# right.net
KiCad netlist of a schematic drawn in EAGLE
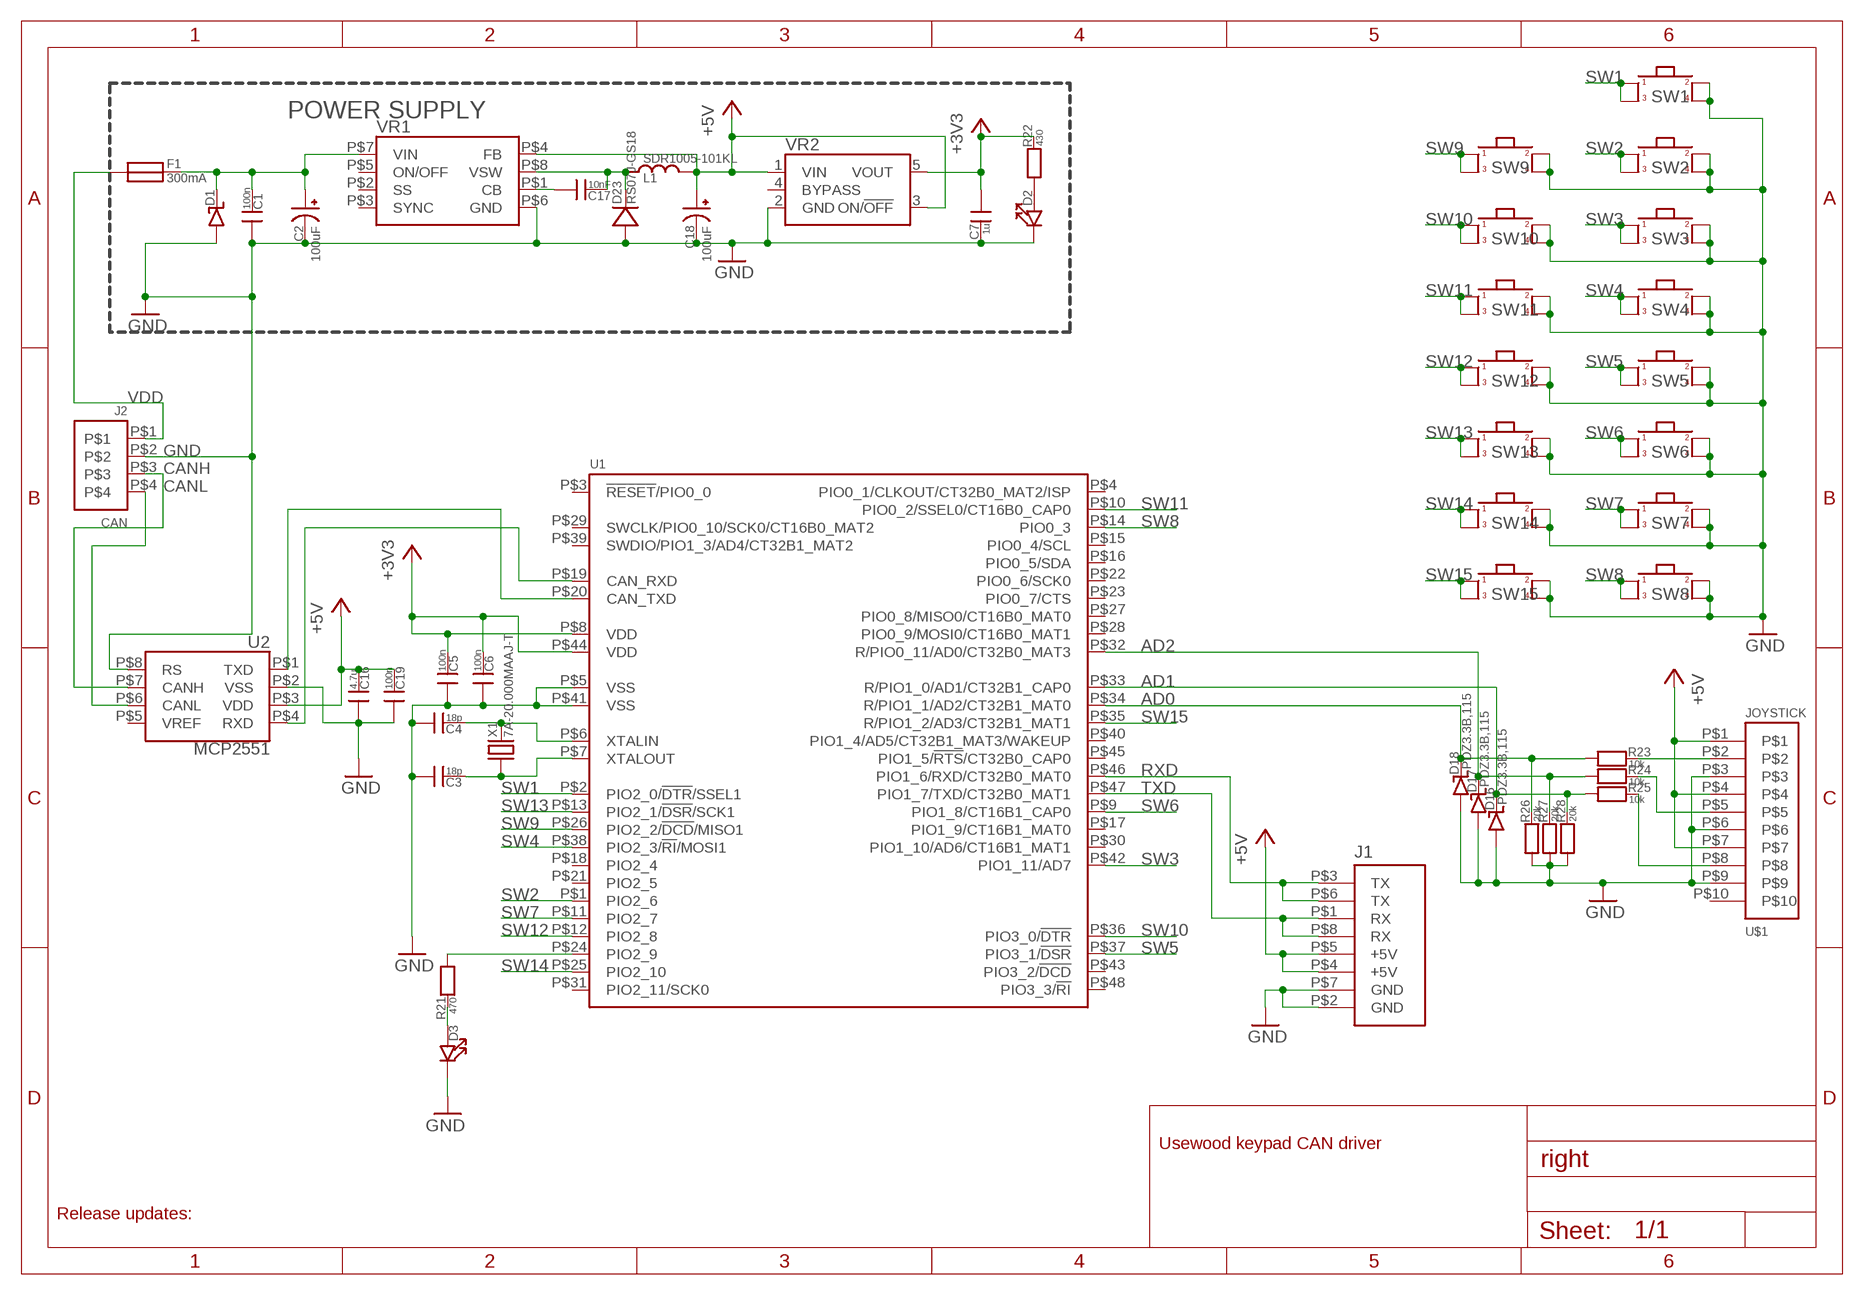
[diagram p0: schematic, sheet 1]

(export (version "E")
  (design (tool "Eeschema 10.0.6"))
  (components
    (comp (ref "C1")
      (value "100n")
      (footprint "eagle-import:0603_SILKSCREEN")
      (libsource (lib "eagle-import") (part "CAP_0603"))
    )
    (comp (ref "C2")
      (value "100uF")
      (footprint "eagle-import:CAP_POL_SMD_10X10X10MM")
      (libsource (lib "eagle-import") (part "CAP_POLSMD_10X10X10MM"))
    )
    (comp (ref "C3")
      (value "18p")
      (footprint "eagle-import:0603_SILKSCREEN")
      (libsource (lib "eagle-import") (part "CAP_0603"))
    )
    (comp (ref "C4")
      (value "18p")
      (footprint "eagle-import:0603_SILKSCREEN")
      (libsource (lib "eagle-import") (part "CAP_0603"))
    )
    (comp (ref "C5")
      (value "100n")
      (footprint "eagle-import:0603_SILKSCREEN")
      (libsource (lib "eagle-import") (part "CAP_0603"))
    )
    (comp (ref "C6")
      (value "100n")
      (footprint "eagle-import:0603_SILKSCREEN")
      (libsource (lib "eagle-import") (part "CAP_0603"))
    )
    (comp (ref "C7")
      (value "1u")
      (footprint "eagle-import:0603_SILKSCREEN")
      (libsource (lib "eagle-import") (part "CAP_0603"))
    )
    (comp (ref "C16")
      (value "4.7u")
      (footprint "eagle-import:0603_SILKSCREEN")
      (libsource (lib "eagle-import") (part "CAP_0603"))
    )
    (comp (ref "C17")
      (value "10nF")
      (footprint "eagle-import:0603_SILKSCREEN")
      (libsource (lib "eagle-import") (part "CAP_0603"))
    )
    (comp (ref "C18")
      (value "100uF")
      (footprint "eagle-import:CAP_POL_SMD_10X10X10MM")
      (libsource (lib "eagle-import") (part "CAP_POLSMD_10X10X10MM"))
    )
    (comp (ref "C19")
      (value "100n")
      (footprint "eagle-import:0603_SILKSCREEN")
      (libsource (lib "eagle-import") (part "CAP_0603"))
    )
    (comp (ref "D1")
      (value "DIODE_TVS_SMBJ33A-TRDO-214AA")
      (footprint "eagle-import:DO-214AA")
      (libsource (lib "eagle-import") (part "DIODE_TVS_SMBJ33A-TRDO-214AA"))
    )
    (comp (ref "D2")
      (value "LED_0603")
      (footprint "eagle-import:0603_SILKSCREEN")
      (libsource (lib "eagle-import") (part "LED_0603"))
    )
    (comp (ref "D3")
      (value "LED_0603")
      (footprint "eagle-import:0603_SILKSCREEN")
      (libsource (lib "eagle-import") (part "LED_0603"))
    )
    (comp (ref "D16")
      (value "PDZ3.3B,115")
      (footprint "eagle-import:SOD123")
      (libsource (lib "eagle-import") (part "DIODE_ZENERSDO123"))
    )
    (comp (ref "D17")
      (value "PDZ3.3B,115")
      (footprint "eagle-import:SOD123")
      (libsource (lib "eagle-import") (part "DIODE_ZENERSDO123"))
    )
    (comp (ref "D18")
      (value "PDZ3.3B,115")
      (footprint "eagle-import:SOD123")
      (libsource (lib "eagle-import") (part "DIODE_ZENERSDO123"))
    )
    (comp (ref "D23")
      (value "RS07J-GS18")
      (footprint "eagle-import:DO219AB")
      (libsource (lib "eagle-import") (part "DIODEDO219AB"))
    )
    (comp (ref "F1")
      (value "300mA")
      (footprint "eagle-import:FUSE_100MA")
      (libsource (lib "eagle-import") (part "FUSE_MC36204_100MA"))
    )
    (comp (ref "J1")
      (value "HEADER_USART_2_SMD")
      (footprint "eagle-import:HEADER_4_2_SMD")
      (libsource (lib "eagle-import") (part "HEADER_USART_2_SMD"))
    )
    (comp (ref "J2")
      (value "CAN")
      (footprint "eagle-import:MOLEX_MICRO_FIT_4WAY_SMD")
      (libsource (lib "eagle-import") (part "MOLEX_MICRO-FIT_4WAY_SMD"))
    )
    (comp (ref "L1")
      (value "SDR1005-101KL")
      (footprint "eagle-import:INDUCTOR_BOURNS_10X13X5MM")
      (libsource (lib "eagle-import") (part "INDUCTORBOURNS_10X13X5MM"))
    )
    (comp (ref "R21")
      (value "470")
      (footprint "eagle-import:0603_SILKSCREEN")
      (libsource (lib "eagle-import") (part "RES_0603"))
    )
    (comp (ref "R22")
      (value "430")
      (footprint "eagle-import:0603_SILKSCREEN")
      (libsource (lib "eagle-import") (part "RES_0603"))
    )
    (comp (ref "R23")
      (value "10k")
      (footprint "eagle-import:0603_SILKSCREEN")
      (libsource (lib "eagle-import") (part "RES_0603"))
    )
    (comp (ref "R24")
      (value "10k")
      (footprint "eagle-import:0603_SILKSCREEN")
      (libsource (lib "eagle-import") (part "RES_0603"))
    )
    (comp (ref "R25")
      (value "10k")
      (footprint "eagle-import:0603_SILKSCREEN")
      (libsource (lib "eagle-import") (part "RES_0603"))
    )
    (comp (ref "R26")
      (value "20k")
      (footprint "eagle-import:0603_SILKSCREEN")
      (libsource (lib "eagle-import") (part "RES_0603"))
    )
    (comp (ref "R27")
      (value "20k")
      (footprint "eagle-import:0603_SILKSCREEN")
      (libsource (lib "eagle-import") (part "RES_0603"))
    )
    (comp (ref "R28")
      (value "20k")
      (footprint "eagle-import:0603_SILKSCREEN")
      (libsource (lib "eagle-import") (part "RES_0603"))
    )
    (comp (ref "SW1")
      (value "SWITCH_KMR231G")
      (footprint "eagle-import:SWITCH_KMR231")
      (libsource (lib "eagle-import") (part "SWITCH_KMR231G"))
    )
    (comp (ref "SW2")
      (value "SWITCH_KMR231G")
      (footprint "eagle-import:SWITCH_KMR231")
      (libsource (lib "eagle-import") (part "SWITCH_KMR231G"))
    )
    (comp (ref "SW3")
      (value "SWITCH_KMR231G")
      (footprint "eagle-import:SWITCH_KMR231")
      (libsource (lib "eagle-import") (part "SWITCH_KMR231G"))
    )
    (comp (ref "SW4")
      (value "SWITCH_KMR231G")
      (footprint "eagle-import:SWITCH_KMR231")
      (libsource (lib "eagle-import") (part "SWITCH_KMR231G"))
    )
    (comp (ref "SW5")
      (value "SWITCH_KMR231G")
      (footprint "eagle-import:SWITCH_KMR231")
      (libsource (lib "eagle-import") (part "SWITCH_KMR231G"))
    )
    (comp (ref "SW6")
      (value "SWITCH_KMR231G")
      (footprint "eagle-import:SWITCH_KMR231")
      (libsource (lib "eagle-import") (part "SWITCH_KMR231G"))
    )
    (comp (ref "SW7")
      (value "SWITCH_KMR231G")
      (footprint "eagle-import:SWITCH_KMR231")
      (libsource (lib "eagle-import") (part "SWITCH_KMR231G"))
    )
    (comp (ref "SW8")
      (value "SWITCH_KMR231G")
      (footprint "eagle-import:SWITCH_KMR231")
      (libsource (lib "eagle-import") (part "SWITCH_KMR231G"))
    )
    (comp (ref "SW9")
      (value "SWITCH_KMR231G")
      (footprint "eagle-import:SWITCH_KMR231")
      (libsource (lib "eagle-import") (part "SWITCH_KMR231G"))
    )
    (comp (ref "SW10")
      (value "SWITCH_KMR231G")
      (footprint "eagle-import:SWITCH_KMR231")
      (libsource (lib "eagle-import") (part "SWITCH_KMR231G"))
    )
    (comp (ref "SW11")
      (value "SWITCH_KMR231G")
      (footprint "eagle-import:SWITCH_KMR231")
      (libsource (lib "eagle-import") (part "SWITCH_KMR231G"))
    )
    (comp (ref "SW12")
      (value "SWITCH_KMR231G")
      (footprint "eagle-import:SWITCH_KMR231")
      (libsource (lib "eagle-import") (part "SWITCH_KMR231G"))
    )
    (comp (ref "SW13")
      (value "SWITCH_KMR231G")
      (footprint "eagle-import:SWITCH_KMR231")
      (libsource (lib "eagle-import") (part "SWITCH_KMR231G"))
    )
    (comp (ref "SW14")
      (value "SWITCH_KMR231G")
      (footprint "eagle-import:SWITCH_KMR231")
      (libsource (lib "eagle-import") (part "SWITCH_KMR231G"))
    )
    (comp (ref "SW15")
      (value "SWITCH_KMR231G")
      (footprint "eagle-import:SWITCH_KMR231")
      (libsource (lib "eagle-import") (part "SWITCH_KMR231G"))
    )
    (comp (ref "U$1")
      (value "JOYSTICK")
      (footprint "eagle-import:MOLEX-MICRO-FIT_10WAY")
      (libsource (lib "eagle-import") (part "MOLEX_MICRO-FIT_10WAY_TH"))
    )
    (comp (ref "U1")
      (value "LPC11C14_QFP48")
      (footprint "eagle-import:QFP48")
      (libsource (lib "eagle-import") (part "LPC11C14_QFP48"))
    )
    (comp (ref "U2")
      (value "MCP2551")
      (footprint "eagle-import:SOIC8")
      (libsource (lib "eagle-import") (part "MCP2551_SOIC8"))
    )
    (comp (ref "VR1")
      (value "LM2671SOIC8")
      (footprint "eagle-import:SOIC8")
      (libsource (lib "eagle-import") (part "LM2671SOIC8"))
    )
    (comp (ref "VR2")
      (value "REG_LP2985_SOP5")
      (footprint "eagle-import:SOP5")
      (libsource (lib "eagle-import") (part "REG_LP2985_SOP5"))
    )
    (comp (ref "X1")
      (value "7A-20.000MAAJ-T")
      (footprint "eagle-import:XTAL_SMD_5X3.2")
      (libsource (lib "eagle-import") (part "XTAL_7A-12.000MAAJ-T"))
    )
  )
  (nets
    (net (code "1") (name "+3V3") (class "Default")
      (node (ref "C5") (pin "1") (pinfunction "P$2_1") (pintype "bidirectional"))
      (node (ref "C6") (pin "1") (pinfunction "P$2_1") (pintype "bidirectional"))
      (node (ref "C7") (pin "0") (pinfunction "P$1_0") (pintype "bidirectional"))
      (node (ref "R22") (pin "1") (pinfunction "P$2_1") (pintype "bidirectional"))
      (node (ref "U1") (pin "P$44") (pinfunction "VDD_P$44") (pintype "bidirectional"))
      (node (ref "U1") (pin "P$8") (pinfunction "VDD_P$8") (pintype "bidirectional"))
      (node (ref "VR2") (pin "5") (pinfunction "VOUT_5") (pintype "bidirectional"))
    )
    (net (code "2") (name "+5V") (class "Default")
      (node (ref "C16") (pin "1") (pinfunction "P$2_1") (pintype "bidirectional"))
      (node (ref "C18") (pin "+") (pinfunction "+_+") (pintype "bidirectional"))
      (node (ref "C19") (pin "1") (pinfunction "P$2_1") (pintype "bidirectional"))
      (node (ref "J1") (pin "P$4") (pinfunction "+5V_P$4") (pintype "bidirectional"))
      (node (ref "J1") (pin "P$5") (pinfunction "+5V_P$5") (pintype "bidirectional"))
      (node (ref "L1") (pin "P$2") (pinfunction "P$2_P$2") (pintype "bidirectional"))
      (node (ref "U$1") (pin "P$1") (pinfunction "P$1_P$1") (pintype "bidirectional"))
      (node (ref "U$1") (pin "P$4") (pinfunction "P$4_P$4") (pintype "bidirectional"))
      (node (ref "U$1") (pin "P$7") (pinfunction "P$7_P$7") (pintype "bidirectional"))
      (node (ref "U2") (pin "P$3") (pinfunction "VDD_P$3") (pintype "bidirectional"))
      (node (ref "VR1") (pin "P$4") (pinfunction "FB_P$4") (pintype "bidirectional"))
      (node (ref "VR2") (pin "1") (pinfunction "VIN_1") (pintype "bidirectional"))
      (node (ref "VR2") (pin "3") (pinfunction "ON/~{OFF}_3") (pintype "bidirectional"))
    )
    (net (code "3") (name "/AD0") (class "Default")
      (node (ref "D18") (pin "P$2") (pinfunction "N_P$2") (pintype "bidirectional"))
      (node (ref "R23") (pin "0") (pinfunction "P$1_0") (pintype "bidirectional"))
      (node (ref "R26") (pin "1") (pinfunction "P$2_1") (pintype "bidirectional"))
      (node (ref "U1") (pin "P$34") (pinfunction "R/PIO1_1/AD2/CT32B1_MAT0_P$34") (pintype "bidirectional"))
    )
    (net (code "4") (name "/AD1") (class "Default")
      (node (ref "D16") (pin "P$2") (pinfunction "N_P$2") (pintype "bidirectional"))
      (node (ref "R25") (pin "0") (pinfunction "P$1_0") (pintype "bidirectional"))
      (node (ref "R28") (pin "1") (pinfunction "P$2_1") (pintype "bidirectional"))
      (node (ref "U1") (pin "P$33") (pinfunction "R/PIO1_0/AD1/CT32B1_CAP0_P$33") (pintype "bidirectional"))
    )
    (net (code "5") (name "/AD2") (class "Default")
      (node (ref "D17") (pin "P$2") (pinfunction "N_P$2") (pintype "bidirectional"))
      (node (ref "R24") (pin "0") (pinfunction "P$1_0") (pintype "bidirectional"))
      (node (ref "R27") (pin "1") (pinfunction "P$2_1") (pintype "bidirectional"))
      (node (ref "U1") (pin "P$32") (pinfunction "R/PIO0_11/AD0/CT32B0_MAT3_P$32") (pintype "bidirectional"))
    )
    (net (code "6") (name "/CANH") (class "Default")
      (node (ref "J2") (pin "P$3") (pinfunction "P$3_P$3") (pintype "bidirectional"))
      (node (ref "U2") (pin "P$7") (pinfunction "CANH_P$7") (pintype "bidirectional"))
    )
    (net (code "7") (name "/CANL") (class "Default")
      (node (ref "J2") (pin "P$4") (pinfunction "P$4_P$4") (pintype "bidirectional"))
      (node (ref "U2") (pin "P$6") (pinfunction "CANL_P$6") (pintype "bidirectional"))
    )
    (net (code "8") (name "/RXD") (class "Default")
      (node (ref "J1") (pin "P$3") (pinfunction "TX_P$3") (pintype "bidirectional"))
      (node (ref "J1") (pin "P$6") (pinfunction "TX_P$6") (pintype "bidirectional"))
      (node (ref "U1") (pin "P$46") (pinfunction "PIO1_6/RXD/CT32B0_MAT0_P$46") (pintype "bidirectional"))
    )
    (net (code "9") (name "/SW1") (class "Default")
      (node (ref "SW1") (pin "P$1") (pinfunction "P$1_P$1") (pintype "bidirectional"))
      (node (ref "SW1") (pin "P$3") (pinfunction "P$3_P$3") (pintype "bidirectional"))
      (node (ref "U1") (pin "P$2") (pinfunction "PIO2_0/~{DTR}/SSEL1_P$2") (pintype "bidirectional"))
    )
    (net (code "10") (name "/SW2") (class "Default")
      (node (ref "SW2") (pin "P$1") (pinfunction "P$1_P$1") (pintype "bidirectional"))
      (node (ref "SW2") (pin "P$3") (pinfunction "P$3_P$3") (pintype "bidirectional"))
      (node (ref "U1") (pin "P$1") (pinfunction "PIO2_6_P$1") (pintype "bidirectional"))
    )
    (net (code "11") (name "/SW3") (class "Default")
      (node (ref "SW3") (pin "P$1") (pinfunction "P$1_P$1") (pintype "bidirectional"))
      (node (ref "SW3") (pin "P$3") (pinfunction "P$3_P$3") (pintype "bidirectional"))
      (node (ref "U1") (pin "P$42") (pinfunction "PIO1_11/AD7_P$42") (pintype "bidirectional"))
    )
    (net (code "12") (name "/SW4") (class "Default")
      (node (ref "SW4") (pin "P$1") (pinfunction "P$1_P$1") (pintype "bidirectional"))
      (node (ref "SW4") (pin "P$3") (pinfunction "P$3_P$3") (pintype "bidirectional"))
      (node (ref "U1") (pin "P$38") (pinfunction "PIO2_3/~{RI}/MOSI1_P$38") (pintype "bidirectional"))
    )
    (net (code "13") (name "/SW5") (class "Default")
      (node (ref "SW5") (pin "P$1") (pinfunction "P$1_P$1") (pintype "bidirectional"))
      (node (ref "SW5") (pin "P$3") (pinfunction "P$3_P$3") (pintype "bidirectional"))
      (node (ref "U1") (pin "P$37") (pinfunction "PIO3_1/~{DSR}_P$37") (pintype "bidirectional"))
    )
    (net (code "14") (name "/SW6") (class "Default")
      (node (ref "SW6") (pin "P$1") (pinfunction "P$1_P$1") (pintype "bidirectional"))
      (node (ref "SW6") (pin "P$3") (pinfunction "P$3_P$3") (pintype "bidirectional"))
      (node (ref "U1") (pin "P$9") (pinfunction "PIO1_8/CT16B1_CAP0_P$9") (pintype "bidirectional"))
    )
    (net (code "15") (name "/SW7") (class "Default")
      (node (ref "SW7") (pin "P$1") (pinfunction "P$1_P$1") (pintype "bidirectional"))
      (node (ref "SW7") (pin "P$3") (pinfunction "P$3_P$3") (pintype "bidirectional"))
      (node (ref "U1") (pin "P$11") (pinfunction "PIO2_7_P$11") (pintype "bidirectional"))
    )
    (net (code "16") (name "/SW8") (class "Default")
      (node (ref "SW8") (pin "P$1") (pinfunction "P$1_P$1") (pintype "bidirectional"))
      (node (ref "SW8") (pin "P$3") (pinfunction "P$3_P$3") (pintype "bidirectional"))
      (node (ref "U1") (pin "P$14") (pinfunction "PIO0_3_P$14") (pintype "bidirectional"))
    )
    (net (code "17") (name "/SW9") (class "Default")
      (node (ref "SW9") (pin "P$1") (pinfunction "P$1_P$1") (pintype "bidirectional"))
      (node (ref "SW9") (pin "P$3") (pinfunction "P$3_P$3") (pintype "bidirectional"))
      (node (ref "U1") (pin "P$26") (pinfunction "PIO2_2/~{DCD}/MISO1_P$26") (pintype "bidirectional"))
    )
    (net (code "18") (name "/SW10") (class "Default")
      (node (ref "SW10") (pin "P$1") (pinfunction "P$1_P$1") (pintype "bidirectional"))
      (node (ref "SW10") (pin "P$3") (pinfunction "P$3_P$3") (pintype "bidirectional"))
      (node (ref "U1") (pin "P$36") (pinfunction "PIO3_0/~{DTR}_P$36") (pintype "bidirectional"))
    )
    (net (code "19") (name "/SW11") (class "Default")
      (node (ref "SW11") (pin "P$1") (pinfunction "P$1_P$1") (pintype "bidirectional"))
      (node (ref "SW11") (pin "P$3") (pinfunction "P$3_P$3") (pintype "bidirectional"))
      (node (ref "U1") (pin "P$10") (pinfunction "PIO0_2/SSEL0/CT16B0_CAP0_P$10") (pintype "bidirectional"))
    )
    (net (code "20") (name "/SW12") (class "Default")
      (node (ref "SW12") (pin "P$1") (pinfunction "P$1_P$1") (pintype "bidirectional"))
      (node (ref "SW12") (pin "P$3") (pinfunction "P$3_P$3") (pintype "bidirectional"))
      (node (ref "U1") (pin "P$12") (pinfunction "PIO2_8_P$12") (pintype "bidirectional"))
    )
    (net (code "21") (name "/SW13") (class "Default")
      (node (ref "SW13") (pin "P$1") (pinfunction "P$1_P$1") (pintype "bidirectional"))
      (node (ref "SW13") (pin "P$3") (pinfunction "P$3_P$3") (pintype "bidirectional"))
      (node (ref "U1") (pin "P$13") (pinfunction "PIO2_1/~{DSR}/SCK1_P$13") (pintype "bidirectional"))
    )
    (net (code "22") (name "/SW14") (class "Default")
      (node (ref "SW14") (pin "P$1") (pinfunction "P$1_P$1") (pintype "bidirectional"))
      (node (ref "SW14") (pin "P$3") (pinfunction "P$3_P$3") (pintype "bidirectional"))
      (node (ref "U1") (pin "P$25") (pinfunction "PIO2_10_P$25") (pintype "bidirectional"))
    )
    (net (code "23") (name "/SW15") (class "Default")
      (node (ref "SW15") (pin "P$1") (pinfunction "P$1_P$1") (pintype "bidirectional"))
      (node (ref "SW15") (pin "P$3") (pinfunction "P$3_P$3") (pintype "bidirectional"))
      (node (ref "U1") (pin "P$35") (pinfunction "R/PIO1_2/AD3/CT32B1_MAT1_P$35") (pintype "bidirectional"))
    )
    (net (code "24") (name "/TXD") (class "Default")
      (node (ref "J1") (pin "P$1") (pinfunction "RX_P$1") (pintype "bidirectional"))
      (node (ref "J1") (pin "P$8") (pinfunction "RX_P$8") (pintype "bidirectional"))
      (node (ref "U1") (pin "P$47") (pinfunction "PIO1_7/TXD/CT32B0_MAT1_P$47") (pintype "bidirectional"))
    )
    (net (code "25") (name "/VDD") (class "Default")
      (node (ref "F1") (pin "P$1") (pinfunction "P$1_P$1") (pintype "bidirectional"))
      (node (ref "J2") (pin "P$1") (pinfunction "P$1_P$1") (pintype "bidirectional"))
    )
    (net (code "26") (name "GND") (class "Default")
      (node (ref "C1") (pin "0") (pinfunction "P$1_0") (pintype "bidirectional"))
      (node (ref "C16") (pin "0") (pinfunction "P$1_0") (pintype "bidirectional"))
      (node (ref "C18") (pin "-") (pinfunction "-_-") (pintype "bidirectional"))
      (node (ref "C19") (pin "0") (pinfunction "P$1_0") (pintype "bidirectional"))
      (node (ref "C2") (pin "-") (pinfunction "-_-") (pintype "bidirectional"))
      (node (ref "C3") (pin "0") (pinfunction "P$1_0") (pintype "bidirectional"))
      (node (ref "C4") (pin "0") (pinfunction "P$1_0") (pintype "bidirectional"))
      (node (ref "C5") (pin "0") (pinfunction "P$1_0") (pintype "bidirectional"))
      (node (ref "C6") (pin "0") (pinfunction "P$1_0") (pintype "bidirectional"))
      (node (ref "C7") (pin "1") (pinfunction "P$2_1") (pintype "bidirectional"))
      (node (ref "D1") (pin "P$1") (pinfunction "P_P$1") (pintype "bidirectional"))
      (node (ref "D16") (pin "P$1") (pinfunction "P_P$1") (pintype "bidirectional"))
      (node (ref "D17") (pin "P$1") (pinfunction "P_P$1") (pintype "bidirectional"))
      (node (ref "D18") (pin "P$1") (pinfunction "P_P$1") (pintype "bidirectional"))
      (node (ref "D2") (pin "1") (pinfunction "1_1") (pintype "bidirectional"))
      (node (ref "D23") (pin "P$1") (pinfunction "P_P$1") (pintype "bidirectional"))
      (node (ref "D3") (pin "1") (pinfunction "1_1") (pintype "bidirectional"))
      (node (ref "J1") (pin "P$2") (pinfunction "GND_P$2") (pintype "bidirectional"))
      (node (ref "J1") (pin "P$7") (pinfunction "GND_P$7") (pintype "bidirectional"))
      (node (ref "J2") (pin "P$2") (pinfunction "P$2_P$2") (pintype "bidirectional"))
      (node (ref "R26") (pin "0") (pinfunction "P$1_0") (pintype "bidirectional"))
      (node (ref "R27") (pin "0") (pinfunction "P$1_0") (pintype "bidirectional"))
      (node (ref "R28") (pin "0") (pinfunction "P$1_0") (pintype "bidirectional"))
      (node (ref "SW1") (pin "P$2") (pinfunction "P$2_P$2") (pintype "bidirectional"))
      (node (ref "SW1") (pin "P$4") (pinfunction "P$4_P$4") (pintype "bidirectional"))
      (node (ref "SW10") (pin "P$2") (pinfunction "P$2_P$2") (pintype "bidirectional"))
      (node (ref "SW10") (pin "P$4") (pinfunction "P$4_P$4") (pintype "bidirectional"))
      (node (ref "SW11") (pin "P$2") (pinfunction "P$2_P$2") (pintype "bidirectional"))
      (node (ref "SW11") (pin "P$4") (pinfunction "P$4_P$4") (pintype "bidirectional"))
      (node (ref "SW12") (pin "P$2") (pinfunction "P$2_P$2") (pintype "bidirectional"))
      (node (ref "SW12") (pin "P$4") (pinfunction "P$4_P$4") (pintype "bidirectional"))
      (node (ref "SW13") (pin "P$2") (pinfunction "P$2_P$2") (pintype "bidirectional"))
      (node (ref "SW13") (pin "P$4") (pinfunction "P$4_P$4") (pintype "bidirectional"))
      (node (ref "SW14") (pin "P$2") (pinfunction "P$2_P$2") (pintype "bidirectional"))
      (node (ref "SW14") (pin "P$4") (pinfunction "P$4_P$4") (pintype "bidirectional"))
      (node (ref "SW15") (pin "P$2") (pinfunction "P$2_P$2") (pintype "bidirectional"))
      (node (ref "SW15") (pin "P$4") (pinfunction "P$4_P$4") (pintype "bidirectional"))
      (node (ref "SW2") (pin "P$2") (pinfunction "P$2_P$2") (pintype "bidirectional"))
      (node (ref "SW2") (pin "P$4") (pinfunction "P$4_P$4") (pintype "bidirectional"))
      (node (ref "SW3") (pin "P$2") (pinfunction "P$2_P$2") (pintype "bidirectional"))
      (node (ref "SW3") (pin "P$4") (pinfunction "P$4_P$4") (pintype "bidirectional"))
      (node (ref "SW4") (pin "P$2") (pinfunction "P$2_P$2") (pintype "bidirectional"))
      (node (ref "SW4") (pin "P$4") (pinfunction "P$4_P$4") (pintype "bidirectional"))
      (node (ref "SW5") (pin "P$2") (pinfunction "P$2_P$2") (pintype "bidirectional"))
      (node (ref "SW5") (pin "P$4") (pinfunction "P$4_P$4") (pintype "bidirectional"))
      (node (ref "SW6") (pin "P$2") (pinfunction "P$2_P$2") (pintype "bidirectional"))
      (node (ref "SW6") (pin "P$4") (pinfunction "P$4_P$4") (pintype "bidirectional"))
      (node (ref "SW7") (pin "P$2") (pinfunction "P$2_P$2") (pintype "bidirectional"))
      (node (ref "SW7") (pin "P$4") (pinfunction "P$4_P$4") (pintype "bidirectional"))
      (node (ref "SW8") (pin "P$2") (pinfunction "P$2_P$2") (pintype "bidirectional"))
      (node (ref "SW8") (pin "P$4") (pinfunction "P$4_P$4") (pintype "bidirectional"))
      (node (ref "SW9") (pin "P$2") (pinfunction "P$2_P$2") (pintype "bidirectional"))
      (node (ref "SW9") (pin "P$4") (pinfunction "P$4_P$4") (pintype "bidirectional"))
      (node (ref "U$1") (pin "P$3") (pinfunction "P$3_P$3") (pintype "bidirectional"))
      (node (ref "U$1") (pin "P$6") (pinfunction "P$6_P$6") (pintype "bidirectional"))
      (node (ref "U$1") (pin "P$9") (pinfunction "P$9_P$9") (pintype "bidirectional"))
      (node (ref "U1") (pin "P$41") (pinfunction "VSS_P$41") (pintype "bidirectional"))
      (node (ref "U1") (pin "P$5") (pinfunction "VSS_P$5") (pintype "bidirectional"))
      (node (ref "U2") (pin "P$2") (pinfunction "VSS_P$2") (pintype "bidirectional"))
      (node (ref "U2") (pin "P$8") (pinfunction "RS_P$8") (pintype "bidirectional"))
      (node (ref "VR1") (pin "P$6") (pinfunction "GND_P$6") (pintype "bidirectional"))
      (node (ref "VR2") (pin "2") (pinfunction "GND_2") (pintype "bidirectional"))
    )
    (net (code "27") (name "Net-(C1-P$2)") (class "Default")
      (node (ref "C1") (pin "1") (pinfunction "P$2_1") (pintype "bidirectional"))
      (node (ref "C2") (pin "+") (pinfunction "+_+") (pintype "bidirectional"))
      (node (ref "D1") (pin "P$2") (pinfunction "N_P$2") (pintype "bidirectional"))
      (node (ref "F1") (pin "P$2") (pinfunction "P$2_P$2") (pintype "bidirectional"))
      (node (ref "VR1") (pin "P$7") (pinfunction "VIN_P$7") (pintype "bidirectional"))
    )
    (net (code "28") (name "Net-(C3-P$2)") (class "Default")
      (node (ref "C3") (pin "1") (pinfunction "P$2_1") (pintype "bidirectional"))
      (node (ref "U1") (pin "P$7") (pinfunction "XTALOUT_P$7") (pintype "bidirectional"))
      (node (ref "X1") (pin "P$1") (pinfunction "P$1_P$1") (pintype "bidirectional"))
    )
    (net (code "29") (name "Net-(C4-P$2)") (class "Default")
      (node (ref "C4") (pin "1") (pinfunction "P$2_1") (pintype "bidirectional"))
      (node (ref "U1") (pin "P$6") (pinfunction "XTALIN_P$6") (pintype "bidirectional"))
      (node (ref "X1") (pin "P$2") (pinfunction "P$2_P$2") (pintype "bidirectional"))
    )
    (net (code "30") (name "Net-(C17-P$1)") (class "Default")
      (node (ref "C17") (pin "0") (pinfunction "P$1_0") (pintype "bidirectional"))
      (node (ref "VR1") (pin "P$1") (pinfunction "CB_P$1") (pintype "bidirectional"))
    )
    (net (code "31") (name "Net-(C17-P$2)") (class "Default")
      (node (ref "C17") (pin "1") (pinfunction "P$2_1") (pintype "bidirectional"))
      (node (ref "D23") (pin "P$2") (pinfunction "N_P$2") (pintype "bidirectional"))
      (node (ref "L1") (pin "P$1") (pinfunction "P$1_P$1") (pintype "bidirectional"))
      (node (ref "VR1") (pin "P$8") (pinfunction "VSW_P$8") (pintype "bidirectional"))
    )
    (net (code "32") (name "Net-(R21-P$1)") (class "Default")
      (node (ref "R21") (pin "0") (pinfunction "P$1_0") (pintype "bidirectional"))
      (node (ref "U1") (pin "P$24") (pinfunction "PIO2_9_P$24") (pintype "bidirectional"))
    )
    (net (code "33") (name "Net-(R21-P$2)") (class "Default")
      (node (ref "D3") (pin "0") (pinfunction "0_0") (pintype "bidirectional"))
      (node (ref "R21") (pin "1") (pinfunction "P$2_1") (pintype "bidirectional"))
    )
    (net (code "34") (name "Net-(R22-P$1)") (class "Default")
      (node (ref "D2") (pin "0") (pinfunction "0_0") (pintype "bidirectional"))
      (node (ref "R22") (pin "0") (pinfunction "P$1_0") (pintype "bidirectional"))
    )
    (net (code "35") (name "Net-(R23-P$2)") (class "Default")
      (node (ref "R23") (pin "1") (pinfunction "P$2_1") (pintype "bidirectional"))
      (node (ref "U$1") (pin "P$2") (pinfunction "P$2_P$2") (pintype "bidirectional"))
    )
    (net (code "36") (name "Net-(R24-P$2)") (class "Default")
      (node (ref "R24") (pin "1") (pinfunction "P$2_1") (pintype "bidirectional"))
      (node (ref "U$1") (pin "P$5") (pinfunction "P$5_P$5") (pintype "bidirectional"))
    )
    (net (code "37") (name "Net-(R25-P$2)") (class "Default")
      (node (ref "R25") (pin "1") (pinfunction "P$2_1") (pintype "bidirectional"))
      (node (ref "U$1") (pin "P$8") (pinfunction "P$8_P$8") (pintype "bidirectional"))
    )
    (net (code "38") (name "Net-(U1-CAN_RXD)") (class "Default")
      (node (ref "U1") (pin "P$19") (pinfunction "CAN_RXD_P$19") (pintype "bidirectional"))
      (node (ref "U2") (pin "P$4") (pinfunction "RXD_P$4") (pintype "bidirectional"))
    )
    (net (code "39") (name "Net-(U1-CAN_TXD)") (class "Default")
      (node (ref "U1") (pin "P$20") (pinfunction "CAN_TXD_P$20") (pintype "bidirectional"))
      (node (ref "U2") (pin "P$1") (pinfunction "TXD_P$1") (pintype "bidirectional"))
    )
    (net (code "40") (name "unconnected-(U$1-PadP$10)") (class "Default")
      (node (ref "U$1") (pin "P$10") (pinfunction "P$10_P$10") (pintype "bidirectional"))
    )
    (net (code "41") (name "unconnected-(U1-PIO0_1{slash}CLKOUT{slash}CT32B0_MAT2{slash}ISP-PadP$4)") (class "Default")
      (node (ref "U1") (pin "P$4") (pinfunction "PIO0_1/CLKOUT/CT32B0_MAT2/ISP_P$4") (pintype "bidirectional"))
    )
    (net (code "42") (name "unconnected-(U1-PIO0_4{slash}SCL-PadP$15)") (class "Default")
      (node (ref "U1") (pin "P$15") (pinfunction "PIO0_4/SCL_P$15") (pintype "bidirectional"))
    )
    (net (code "43") (name "unconnected-(U1-PIO0_5{slash}SDA-PadP$16)") (class "Default")
      (node (ref "U1") (pin "P$16") (pinfunction "PIO0_5/SDA_P$16") (pintype "bidirectional"))
    )
    (net (code "44") (name "unconnected-(U1-PIO0_6{slash}SCK0-PadP$22)") (class "Default")
      (node (ref "U1") (pin "P$22") (pinfunction "PIO0_6/SCK0_P$22") (pintype "bidirectional"))
    )
    (net (code "45") (name "unconnected-(U1-PIO0_7{slash}CTS-PadP$23)") (class "Default")
      (node (ref "U1") (pin "P$23") (pinfunction "PIO0_7/CTS_P$23") (pintype "bidirectional"))
    )
    (net (code "46") (name "unconnected-(U1-PIO0_8{slash}MISO0{slash}CT16B0_MAT0-PadP$27)") (class "Default")
      (node (ref "U1") (pin "P$27") (pinfunction "PIO0_8/MISO0/CT16B0_MAT0_P$27") (pintype "bidirectional"))
    )
    (net (code "47") (name "unconnected-(U1-PIO0_9{slash}MOSI0{slash}CT16B0_MAT1-PadP$28)") (class "Default")
      (node (ref "U1") (pin "P$28") (pinfunction "PIO0_9/MOSI0/CT16B0_MAT1_P$28") (pintype "bidirectional"))
    )
    (net (code "48") (name "unconnected-(U1-PIO1_4{slash}AD5{slash}CT32B1_MAT3{slash}WAKEUP-PadP$40)") (class "Default")
      (node (ref "U1") (pin "P$40") (pinfunction "PIO1_4/AD5/CT32B1_MAT3/WAKEUP_P$40") (pintype "bidirectional"))
    )
    (net (code "49") (name "unconnected-(U1-PIO1_5{slash}~{RTS}{slash}CT32B0_CAP0-PadP$45)") (class "Default")
      (node (ref "U1") (pin "P$45") (pinfunction "PIO1_5/~{RTS}/CT32B0_CAP0_P$45") (pintype "bidirectional"))
    )
    (net (code "50") (name "unconnected-(U1-PIO1_9{slash}CT16B1_MAT0-PadP$17)") (class "Default")
      (node (ref "U1") (pin "P$17") (pinfunction "PIO1_9/CT16B1_MAT0_P$17") (pintype "bidirectional"))
    )
    (net (code "51") (name "unconnected-(U1-PIO1_10{slash}AD6{slash}CT16B1_MAT1-PadP$30)") (class "Default")
      (node (ref "U1") (pin "P$30") (pinfunction "PIO1_10/AD6/CT16B1_MAT1_P$30") (pintype "bidirectional"))
    )
    (net (code "52") (name "unconnected-(U1-PIO2_4-PadP$18)") (class "Default")
      (node (ref "U1") (pin "P$18") (pinfunction "PIO2_4_P$18") (pintype "bidirectional"))
    )
    (net (code "53") (name "unconnected-(U1-PIO2_5-PadP$21)") (class "Default")
      (node (ref "U1") (pin "P$21") (pinfunction "PIO2_5_P$21") (pintype "bidirectional"))
    )
    (net (code "54") (name "unconnected-(U1-PIO2_11{slash}SCK0-PadP$31)") (class "Default")
      (node (ref "U1") (pin "P$31") (pinfunction "PIO2_11/SCK0_P$31") (pintype "bidirectional"))
    )
    (net (code "55") (name "unconnected-(U1-PIO3_2{slash}~{DCD}-PadP$43)") (class "Default")
      (node (ref "U1") (pin "P$43") (pinfunction "PIO3_2/~{DCD}_P$43") (pintype "bidirectional"))
    )
    (net (code "56") (name "unconnected-(U1-PIO3_3{slash}~{RI}-PadP$48)") (class "Default")
      (node (ref "U1") (pin "P$48") (pinfunction "PIO3_3/~{RI}_P$48") (pintype "bidirectional"))
    )
    (net (code "57") (name "unconnected-(U1-SWCLK{slash}PIO0_10{slash}SCK0{slash}CT16B0_MAT2-PadP$29)") (class "Default")
      (node (ref "U1") (pin "P$29") (pinfunction "SWCLK/PIO0_10/SCK0/CT16B0_MAT2_P$29") (pintype "bidirectional"))
    )
    (net (code "58") (name "unconnected-(U1-SWDIO{slash}PIO1_3{slash}AD4{slash}CT32B1_MAT2-PadP$39)") (class "Default")
      (node (ref "U1") (pin "P$39") (pinfunction "SWDIO/PIO1_3/AD4/CT32B1_MAT2_P$39") (pintype "bidirectional"))
    )
    (net (code "59") (name "unconnected-(U1-~{RESET}{slash}PIO0_0-PadP$3)") (class "Default")
      (node (ref "U1") (pin "P$3") (pinfunction "~{RESET}/PIO0_0_P$3") (pintype "bidirectional"))
    )
    (net (code "60") (name "unconnected-(U2-VREF-PadP$5)") (class "Default")
      (node (ref "U2") (pin "P$5") (pinfunction "VREF_P$5") (pintype "bidirectional"))
    )
    (net (code "61") (name "unconnected-(VR1-ON{slash}OFF-PadP$5)") (class "Default")
      (node (ref "VR1") (pin "P$5") (pinfunction "ON/OFF_P$5") (pintype "bidirectional"))
    )
    (net (code "62") (name "unconnected-(VR1-SS-PadP$2)") (class "Default")
      (node (ref "VR1") (pin "P$2") (pinfunction "SS_P$2") (pintype "bidirectional"))
    )
    (net (code "63") (name "unconnected-(VR1-SYNC-PadP$3)") (class "Default")
      (node (ref "VR1") (pin "P$3") (pinfunction "SYNC_P$3") (pintype "bidirectional"))
    )
    (net (code "64") (name "unconnected-(VR2-BYPASS-Pad4)") (class "Default")
      (node (ref "VR2") (pin "4") (pinfunction "BYPASS_4") (pintype "bidirectional"))
    )
  )
)
